# Arduino_extension_connectors.net
KiCad netlist of a schematic drawn in Altium Designer
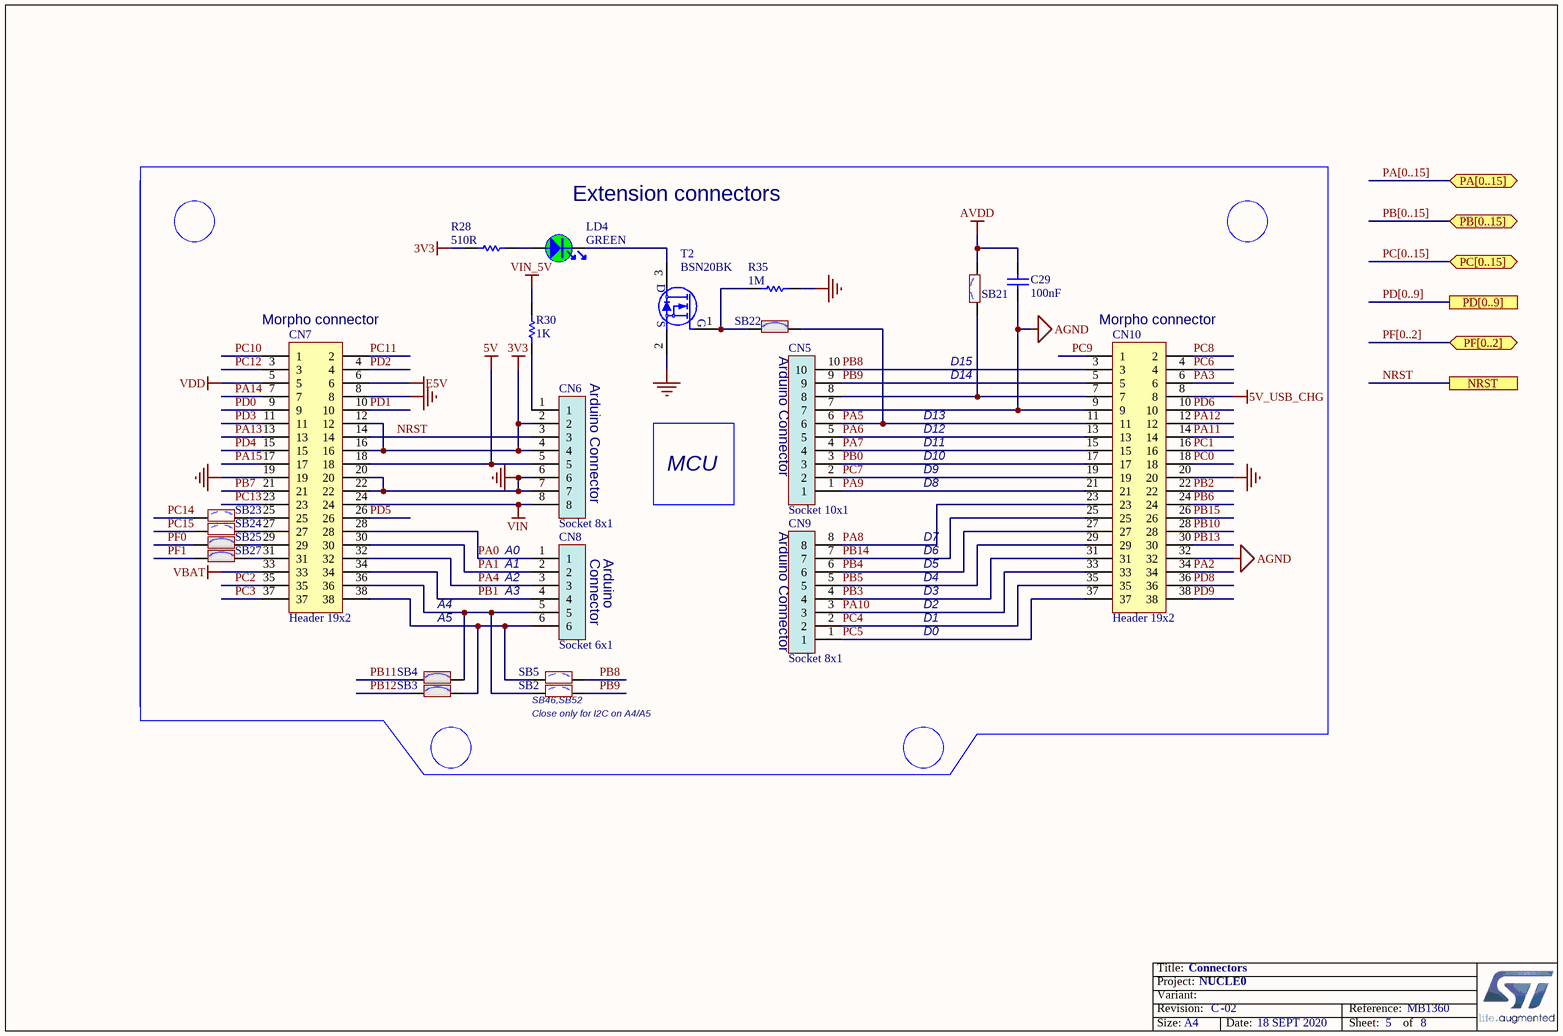
[diagram p0: Arduino_extension_connectors.SchDoc]

(export (version "E")
  (design (tool "Eeschema 10.0.6"))
  (components
    (comp (ref "C29")
      (value "100nF")
      (footprint "C0603")
      (description "Capacitor, MLCC, 100nF, 16V, X7R, 10%, 0603, T=0,8mm")
      (fields
        (field (name "INTERNAL_PART_NUMBER") "MCD-00211")
        (field (name "MANUFACTURER_PART_NUMBER") "CC0603KRX7R7BB104")
        (field (name "PROVIDED_BY") "SUBCO")
      )
      (libsource (lib "MCD_PARTS_database") (part "Capacitor"))
    )
    (comp (ref "CN5")
      (value "Socket 10x1")
      (footprint "CON_SAMTEC_SSW-110-03-X-S")
      (description "Socket, 10x1, 2.54mm, VR, TH, Height 8.51mm/10mm")
      (fields
        (field (name "INTERNAL_PART_NUMBER") "MCD-00262")
        (field (name "MANUFACTURER_PART_NUMBER") "SSW-110-03-x-S")
        (field (name "PROVIDED_BY") "SUBCO")
      )
      (libsource (lib "MCD_PARTS_database") (part "Socket 10x1"))
    )
    (comp (ref "CN6")
      (value "Socket 8x1")
      (footprint "CON_SAMTEC_SSW-108-03-X-S")
      (description "Socket, 8x1, 2.54mm, VR, TH, Height 8.51mm/10mm")
      (fields
        (field (name "INTERNAL_PART_NUMBER") "MCD-00261")
        (field (name "MANUFACTURER_PART_NUMBER") "SSW-108-03-x-S")
        (field (name "PROVIDED_BY") "SUBCO")
      )
      (libsource (lib "MCD_PARTS_database") (part "Socket 8x1"))
    )
    (comp (ref "CN7")
      (value "Header 19x2")
      (footprint "CON_SAMTEC_TSW-119-09-X-D")
      (description "Header, 19x2, 2,54mm, VR, TH, Height 5.84mm/10.16mm")
      (fields
        (field (name "INTERNAL_PART_NUMBER") "MCD-00213")
        (field (name "MANUFACTURER_PART_NUMBER") "TSW-119-09-x-D")
        (field (name "PROVIDED_BY") "SUBCO")
      )
      (libsource (lib "MCD_PARTS_database") (part "Header 19x2"))
    )
    (comp (ref "CN8")
      (value "Socket 6x1")
      (footprint "CON_SAMTEC_SSW-106-03-X-S")
      (description "Socket, 6x1, 2.54mm, VR, TH, Height 8.51mm/10mm")
      (fields
        (field (name "INTERNAL_PART_NUMBER") "MCD-00260")
        (field (name "MANUFACTURER_PART_NUMBER") "SSW-106-03-x-S")
        (field (name "PROVIDED_BY") "SUBCO")
      )
      (libsource (lib "MCD_PARTS_database") (part "Socket 6x1"))
    )
    (comp (ref "CN9")
      (value "Socket 8x1")
      (footprint "CON_SAMTEC_SSW-108-03-X-S")
      (description "Socket, 8x1, 2.54mm, VR, TH, Height 8.51mm/10mm")
      (fields
        (field (name "INTERNAL_PART_NUMBER") "MCD-00261")
        (field (name "MANUFACTURER_PART_NUMBER") "SSW-108-03-x-S")
        (field (name "PROVIDED_BY") "SUBCO")
      )
      (libsource (lib "") (part "Socket 8x1_1"))
    )
    (comp (ref "CN10")
      (value "Header 19x2")
      (footprint "CON_SAMTEC_TSW-119-09-X-D")
      (description "Header, 19x2, 2,54mm, VR, TH, Height 5.84mm/10.16mm")
      (fields
        (field (name "INTERNAL_PART_NUMBER") "MCD-00213")
        (field (name "MANUFACTURER_PART_NUMBER") "TSW-119-09-x-D")
        (field (name "PROVIDED_BY") "SUBCO")
      )
      (libsource (lib "MCD_PARTS_database") (part "Header 19x2"))
    )
    (comp (ref "LD4")
      (value "GREEN")
      (footprint "LED_0603_GREEN")
      (description "LED, Green, 0603")
      (fields
        (field (name "INTERNAL_PART_NUMBER") "MCD-00050")
        (field (name "MANUFACTURER_PART_NUMBER") "19-213SYGC/S530-E2/TR8")
        (field (name "PROVIDED_BY") "SUBCO")
      )
      (libsource (lib "MCD_PARTS_database") (part "LED_green"))
    )
    (comp (ref "R28")
      (value "510R")
      (footprint "R0603")
      (description "Resistor,510R,0603,1%,1/10W")
      (fields
        (field (name "INTERNAL_PART_NUMBER") "MCD-00225")
        (field (name "MANUFACTURER_PART_NUMBER") "RC0603FR-07510RL")
        (field (name "PROVIDED_BY") "SUBCO")
      )
      (libsource (lib "MCD_PARTS_database") (part "Resistor"))
    )
    (comp (ref "R30")
      (value "1K")
      (footprint "R0603")
      (description "Resistor,1K,0603,1%,1/10W")
      (fields
        (field (name "INTERNAL_PART_NUMBER") "MCD-00070")
        (field (name "MANUFACTURER_PART_NUMBER") "RC0603FR-071KL")
        (field (name "PROVIDED_BY") "SUBCO")
      )
      (libsource (lib "MCD_PARTS_database") (part "Resistor"))
    )
    (comp (ref "R35")
      (value "1M")
      (footprint "R0603")
      (description "Resistor,1M,0603,1%,1/10W")
      (fields
        (field (name "INTERNAL_PART_NUMBER") "MCD-00257")
        (field (name "MANUFACTURER_PART_NUMBER") "RC0603FR-071ML")
        (field (name "PROVIDED_BY") "SUBCO")
      )
      (libsource (lib "MCD_PARTS_database") (part "Resistor"))
    )
    (comp (ref "SB2")
      (value "SB_OFF")
      (footprint "SOLDER-BRIDGE_R0603-0R")
      (description "Solder Bridge OFF")
      (fields
        (field (name "INTERNAL_PART_NUMBER") "MCD-00072")
        (field (name "MANUFACTURER_PART_NUMBER") "RC0603JR-070RL")
        (field (name "PROVIDED_BY") "SUBCO")
      )
      (libsource (lib "MCD_PARTS_database") (part "SB_OFF"))
    )
    (comp (ref "SB3")
      (value "SB_ON")
      (footprint "SOLDER-BRIDGE_R0603-0R")
      (description "Solder Bridge ON")
      (fields
        (field (name "INTERNAL_PART_NUMBER") "MCD-00071")
        (field (name "MANUFACTURER_PART_NUMBER") "RC0603JR-070RL")
        (field (name "PROVIDED_BY") "SUBCO")
      )
      (libsource (lib "MCD_PARTS_database") (part "SB_ON"))
    )
    (comp (ref "SB4")
      (value "SB_ON")
      (footprint "SOLDER-BRIDGE_R0603-0R")
      (description "Solder Bridge ON")
      (fields
        (field (name "INTERNAL_PART_NUMBER") "MCD-00071")
        (field (name "MANUFACTURER_PART_NUMBER") "RC0603JR-070RL")
        (field (name "PROVIDED_BY") "SUBCO")
      )
      (libsource (lib "MCD_PARTS_database") (part "SB_ON"))
    )
    (comp (ref "SB5")
      (value "SB_OFF")
      (footprint "SOLDER-BRIDGE_R0603-0R")
      (description "Solder Bridge OFF")
      (fields
        (field (name "INTERNAL_PART_NUMBER") "MCD-00072")
        (field (name "MANUFACTURER_PART_NUMBER") "RC0603JR-070RL")
        (field (name "PROVIDED_BY") "SUBCO")
      )
      (libsource (lib "MCD_PARTS_database") (part "SB_OFF"))
    )
    (comp (ref "SB21")
      (value "SB_OFF")
      (footprint "SOLDER-BRIDGE_R0603-0R")
      (description "Solder Bridge OFF")
      (fields
        (field (name "INTERNAL_PART_NUMBER") "MCD-00072")
        (field (name "MANUFACTURER_PART_NUMBER") "RC0603JR-070RL")
        (field (name "PROVIDED_BY") "SUBCO")
      )
      (libsource (lib "") (part "SB_OFF_1"))
    )
    (comp (ref "SB22")
      (value "SB_ON")
      (footprint "SOLDER-BRIDGE_R0603-0R")
      (description "Solder Bridge ON")
      (fields
        (field (name "INTERNAL_PART_NUMBER") "MCD-00071")
        (field (name "MANUFACTURER_PART_NUMBER") "RC0603JR-070RL")
        (field (name "PROVIDED_BY") "SUBCO")
      )
      (libsource (lib "MCD_PARTS_database") (part "SB_ON"))
    )
    (comp (ref "SB23")
      (value "SB_OFF")
      (footprint "SOLDER-BRIDGE_R0603-0R")
      (description "Solder Bridge OFF")
      (fields
        (field (name "INTERNAL_PART_NUMBER") "MCD-00072")
        (field (name "MANUFACTURER_PART_NUMBER") "RC0603JR-070RL")
        (field (name "PROVIDED_BY") "SUBCO")
      )
      (libsource (lib "MCD_PARTS_database") (part "SB_OFF"))
    )
    (comp (ref "SB24")
      (value "SB_OFF")
      (footprint "SOLDER-BRIDGE_R0603-0R")
      (description "Solder Bridge OFF")
      (fields
        (field (name "INTERNAL_PART_NUMBER") "MCD-00072")
        (field (name "MANUFACTURER_PART_NUMBER") "RC0603JR-070RL")
        (field (name "PROVIDED_BY") "SUBCO")
      )
      (libsource (lib "MCD_PARTS_database") (part "SB_OFF"))
    )
    (comp (ref "SB25")
      (value "SB_ON")
      (footprint "SOLDER-BRIDGE_R0603-0R")
      (description "Solder Bridge ON")
      (fields
        (field (name "INTERNAL_PART_NUMBER") "MCD-00071")
        (field (name "MANUFACTURER_PART_NUMBER") "RC0603JR-070RL")
        (field (name "PROVIDED_BY") "SUBCO")
      )
      (libsource (lib "MCD_PARTS_database") (part "SB_ON"))
    )
    (comp (ref "SB27")
      (value "SB_ON")
      (footprint "SOLDER-BRIDGE_R0603-0R")
      (description "Solder Bridge ON")
      (fields
        (field (name "INTERNAL_PART_NUMBER") "MCD-00071")
        (field (name "MANUFACTURER_PART_NUMBER") "RC0603JR-070RL")
        (field (name "PROVIDED_BY") "SUBCO")
      )
      (libsource (lib "MCD_PARTS_database") (part "SB_ON"))
    )
    (comp (ref "T2")
      (value "BSN20BK")
      (footprint "MOS_SOT23")
      (description "N-channel enhancement mode field-effect transistor")
      (fields
        (field (name "INTERNAL_PART_NUMBER") "MCD-01969")
        (field (name "MANUFACTURER") "NEXPERIA")
        (field (name "PROVIDED_BY") "SUBCO")
      )
      (libsource (lib "MCD_PARTS_database") (part "BSN20"))
    )
  )
  (nets
    (net (code "3") (name "/NRST") (class "Default")
      (node (ref "CN6") (pin "3") (pinfunction "3_3") (pintype "passive"))
      (node (ref "CN7") (pin "14") (pinfunction "14_14") (pintype "passive"))
    )
    (net (code "4") (name "/PA0") (class "Default")
      (node (ref "CN7") (pin "28") (pinfunction "28_28") (pintype "passive"))
      (node (ref "CN8") (pin "1") (pinfunction "1_1") (pintype "passive"))
    )
    (net (code "5") (name "/PA1") (class "Default")
      (node (ref "CN7") (pin "30") (pinfunction "30_30") (pintype "passive"))
      (node (ref "CN8") (pin "2") (pinfunction "2_2") (pintype "passive"))
    )
    (net (code "6") (name "/PA2") (class "Default")
      (node (ref "CN10") (pin "34") (pinfunction "34_34") (pintype "passive"))
    )
    (net (code "7") (name "/PA3") (class "Default")
      (node (ref "CN10") (pin "6") (pinfunction "6_6") (pintype "passive"))
    )
    (net (code "8") (name "/PA4") (class "Default")
      (node (ref "CN7") (pin "32") (pinfunction "32_32") (pintype "passive"))
      (node (ref "CN8") (pin "3") (pinfunction "3_3") (pintype "passive"))
    )
    (net (code "9") (name "/PA5") (class "Default")
      (node (ref "CN10") (pin "11") (pinfunction "11_11") (pintype "passive"))
      (node (ref "CN5") (pin "6") (pinfunction "6_6") (pintype "passive"))
      (node (ref "SB22") (pin "2") (pinfunction "2_2") (pintype "passive"))
    )
    (net (code "10") (name "/PA6") (class "Default")
      (node (ref "CN10") (pin "13") (pinfunction "13_13") (pintype "passive"))
      (node (ref "CN5") (pin "5") (pinfunction "5_5") (pintype "passive"))
    )
    (net (code "11") (name "/PA7") (class "Default")
      (node (ref "CN10") (pin "15") (pinfunction "15_15") (pintype "passive"))
      (node (ref "CN5") (pin "4") (pinfunction "4_4") (pintype "passive"))
    )
    (net (code "12") (name "/PA8") (class "Default")
      (node (ref "CN10") (pin "23") (pinfunction "23_23") (pintype "passive"))
      (node (ref "CN9") (pin "8") (pinfunction "8_8") (pintype "passive"))
    )
    (net (code "13") (name "/PA9") (class "Default")
      (node (ref "CN10") (pin "21") (pinfunction "21_21") (pintype "passive"))
      (node (ref "CN5") (pin "1") (pinfunction "1_1") (pintype "passive"))
    )
    (net (code "14") (name "/PA10") (class "Default")
      (node (ref "CN10") (pin "33") (pinfunction "33_33") (pintype "passive"))
      (node (ref "CN9") (pin "3") (pinfunction "3_3") (pintype "passive"))
    )
    (net (code "15") (name "/PA11") (class "Default")
      (node (ref "CN10") (pin "14") (pinfunction "14_14") (pintype "passive"))
    )
    (net (code "16") (name "/PA12") (class "Default")
      (node (ref "CN10") (pin "12") (pinfunction "12_12") (pintype "passive"))
    )
    (net (code "17") (name "/PA13") (class "Default")
      (node (ref "CN7") (pin "13") (pinfunction "13_13") (pintype "passive"))
    )
    (net (code "18") (name "/PA14") (class "Default")
      (node (ref "CN7") (pin "7") (pinfunction "7_7") (pintype "passive"))
    )
    (net (code "19") (name "/PA15") (class "Default")
      (node (ref "CN7") (pin "17") (pinfunction "17_17") (pintype "passive"))
    )
    (net (code "21") (name "/PB0") (class "Default")
      (node (ref "CN10") (pin "17") (pinfunction "17_17") (pintype "passive"))
      (node (ref "CN5") (pin "3") (pinfunction "3_3") (pintype "passive"))
    )
    (net (code "22") (name "/PB1") (class "Default")
      (node (ref "CN7") (pin "34") (pinfunction "34_34") (pintype "passive"))
      (node (ref "CN8") (pin "4") (pinfunction "4_4") (pintype "passive"))
    )
    (net (code "23") (name "/PB2") (class "Default")
      (node (ref "CN10") (pin "22") (pinfunction "22_22") (pintype "passive"))
    )
    (net (code "24") (name "/PB3") (class "Default")
      (node (ref "CN10") (pin "31") (pinfunction "31_31") (pintype "passive"))
      (node (ref "CN9") (pin "4") (pinfunction "4_4") (pintype "passive"))
    )
    (net (code "25") (name "/PB4") (class "Default")
      (node (ref "CN10") (pin "27") (pinfunction "27_27") (pintype "passive"))
      (node (ref "CN9") (pin "6") (pinfunction "6_6") (pintype "passive"))
    )
    (net (code "26") (name "/PB5") (class "Default")
      (node (ref "CN10") (pin "29") (pinfunction "29_29") (pintype "passive"))
      (node (ref "CN9") (pin "5") (pinfunction "5_5") (pintype "passive"))
    )
    (net (code "27") (name "/PB6") (class "Default")
      (node (ref "CN10") (pin "24") (pinfunction "24_24") (pintype "passive"))
    )
    (net (code "28") (name "/PB7") (class "Default")
      (node (ref "CN7") (pin "21") (pinfunction "21_21") (pintype "passive"))
    )
    (net (code "29") (name "/PB8") (class "Default")
      (node (ref "CN10") (pin "3") (pinfunction "3_3") (pintype "passive"))
      (node (ref "CN5") (pin "10") (pinfunction "10_10") (pintype "passive"))
      (node (ref "SB5") (pin "2") (pinfunction "2_2") (pintype "passive"))
    )
    (net (code "30") (name "/PB9") (class "Default")
      (node (ref "CN10") (pin "5") (pinfunction "5_5") (pintype "passive"))
      (node (ref "CN5") (pin "9") (pinfunction "9_9") (pintype "passive"))
      (node (ref "SB2") (pin "2") (pinfunction "2_2") (pintype "passive"))
    )
    (net (code "31") (name "/PB10") (class "Default")
      (node (ref "CN10") (pin "28") (pinfunction "28_28") (pintype "passive"))
    )
    (net (code "32") (name "/PB11") (class "Default")
      (node (ref "SB4") (pin "1") (pinfunction "1_1") (pintype "passive"))
    )
    (net (code "33") (name "/PB12") (class "Default")
      (node (ref "SB3") (pin "1") (pinfunction "1_1") (pintype "passive"))
    )
    (net (code "34") (name "/PB13") (class "Default")
      (node (ref "CN10") (pin "30") (pinfunction "30_30") (pintype "passive"))
    )
    (net (code "35") (name "/PB14") (class "Default")
      (node (ref "CN10") (pin "25") (pinfunction "25_25") (pintype "passive"))
      (node (ref "CN9") (pin "7") (pinfunction "7_7") (pintype "passive"))
    )
    (net (code "36") (name "/PB15") (class "Default")
      (node (ref "CN10") (pin "26") (pinfunction "26_26") (pintype "passive"))
    )
    (net (code "38") (name "/PC0") (class "Default")
      (node (ref "CN10") (pin "18") (pinfunction "18_18") (pintype "passive"))
    )
    (net (code "39") (name "/PC1") (class "Default")
      (node (ref "CN10") (pin "16") (pinfunction "16_16") (pintype "passive"))
    )
    (net (code "40") (name "/PC2") (class "Default")
      (node (ref "CN7") (pin "35") (pinfunction "35_35") (pintype "passive"))
    )
    (net (code "41") (name "/PC3") (class "Default")
      (node (ref "CN7") (pin "37") (pinfunction "37_37") (pintype "passive"))
    )
    (net (code "42") (name "/PC4") (class "Default")
      (node (ref "CN10") (pin "35") (pinfunction "35_35") (pintype "passive"))
      (node (ref "CN9") (pin "2") (pinfunction "2_2") (pintype "passive"))
    )
    (net (code "43") (name "/PC5") (class "Default")
      (node (ref "CN10") (pin "37") (pinfunction "37_37") (pintype "passive"))
      (node (ref "CN9") (pin "1") (pinfunction "1_1") (pintype "passive"))
    )
    (net (code "44") (name "/PC6") (class "Default")
      (node (ref "CN10") (pin "4") (pinfunction "4_4") (pintype "passive"))
    )
    (net (code "45") (name "/PC7") (class "Default")
      (node (ref "CN10") (pin "19") (pinfunction "19_19") (pintype "passive"))
      (node (ref "CN5") (pin "2") (pinfunction "2_2") (pintype "passive"))
    )
    (net (code "46") (name "/PC8") (class "Default")
      (node (ref "CN10") (pin "2") (pinfunction "2_2") (pintype "passive"))
    )
    (net (code "47") (name "/PC9") (class "Default")
      (node (ref "CN10") (pin "1") (pinfunction "1_1") (pintype "passive"))
    )
    (net (code "48") (name "/PC10") (class "Default")
      (node (ref "CN7") (pin "1") (pinfunction "1_1") (pintype "passive"))
    )
    (net (code "49") (name "/PC11") (class "Default")
      (node (ref "CN7") (pin "2") (pinfunction "2_2") (pintype "passive"))
    )
    (net (code "50") (name "/PC12") (class "Default")
      (node (ref "CN7") (pin "3") (pinfunction "3_3") (pintype "passive"))
    )
    (net (code "51") (name "/PC13") (class "Default")
      (node (ref "CN7") (pin "23") (pinfunction "23_23") (pintype "passive"))
    )
    (net (code "52") (name "/PC14") (class "Default")
      (node (ref "SB23") (pin "1") (pinfunction "1_1") (pintype "passive"))
    )
    (net (code "53") (name "/PC15") (class "Default")
      (node (ref "SB24") (pin "1") (pinfunction "1_1") (pintype "passive"))
    )
    (net (code "55") (name "/PD0") (class "Default")
      (node (ref "CN7") (pin "9") (pinfunction "9_9") (pintype "passive"))
    )
    (net (code "56") (name "/PD1") (class "Default")
      (node (ref "CN7") (pin "10") (pinfunction "10_10") (pintype "passive"))
    )
    (net (code "57") (name "/PD2") (class "Default")
      (node (ref "CN7") (pin "4") (pinfunction "4_4") (pintype "passive"))
    )
    (net (code "58") (name "/PD3") (class "Default")
      (node (ref "CN7") (pin "11") (pinfunction "11_11") (pintype "passive"))
    )
    (net (code "59") (name "/PD4") (class "Default")
      (node (ref "CN7") (pin "15") (pinfunction "15_15") (pintype "passive"))
    )
    (net (code "60") (name "/PD5") (class "Default")
      (node (ref "CN7") (pin "26") (pinfunction "26_26") (pintype "passive"))
    )
    (net (code "61") (name "/PD6") (class "Default")
      (node (ref "CN10") (pin "10") (pinfunction "10_10") (pintype "passive"))
    )
    (net (code "62") (name "/PD8") (class "Default")
      (node (ref "CN10") (pin "36") (pinfunction "36_36") (pintype "passive"))
    )
    (net (code "63") (name "/PD9") (class "Default")
      (node (ref "CN10") (pin "38") (pinfunction "38_38") (pintype "passive"))
    )
    (net (code "65") (name "/PF0") (class "Default")
      (node (ref "SB25") (pin "1") (pinfunction "1_1") (pintype "passive"))
    )
    (net (code "66") (name "/PF1") (class "Default")
      (node (ref "SB27") (pin "1") (pinfunction "1_1") (pintype "passive"))
    )
    (net (code "68") (name "3V3") (class "Default")
      (node (ref "CN6") (pin "2") (pinfunction "2_2") (pintype "passive"))
      (node (ref "CN6") (pin "4") (pinfunction "4_4") (pintype "passive"))
      (node (ref "CN7") (pin "12") (pinfunction "12_12") (pintype "passive"))
      (node (ref "CN7") (pin "16") (pinfunction "16_16") (pintype "passive"))
      (node (ref "R28") (pin "2") (pinfunction "2_2") (pintype "passive"))
    )
    (net (code "69") (name "5V") (class "Default")
      (node (ref "CN6") (pin "5") (pinfunction "5_5") (pintype "passive"))
      (node (ref "CN7") (pin "18") (pinfunction "18_18") (pintype "passive"))
    )
    (net (code "70") (name "5V_USB_CHG") (class "Default")
      (node (ref "CN10") (pin "8") (pinfunction "8_8") (pintype "passive"))
    )
    (net (code "71") (name "AGND") (class "Default")
      (node (ref "C29") (pin "1") (pinfunction "1_1") (pintype "passive"))
      (node (ref "CN10") (pin "32") (pinfunction "32_32") (pintype "passive"))
      (node (ref "CN10") (pin "9") (pinfunction "9_9") (pintype "passive"))
      (node (ref "CN5") (pin "7") (pinfunction "7_7") (pintype "passive"))
    )
    (net (code "72") (name "AVDD") (class "Default")
      (node (ref "C29") (pin "2") (pinfunction "2_2") (pintype "passive"))
      (node (ref "SB21") (pin "2") (pinfunction "2_2") (pintype "passive"))
    )
    (net (code "73") (name "E5V") (class "Default")
      (node (ref "CN7") (pin "6") (pinfunction "6_6") (pintype "passive"))
    )
    (net (code "74") (name "GND") (class "Default")
      (node (ref "CN10") (pin "20") (pinfunction "20_20") (pintype "passive"))
      (node (ref "CN6") (pin "6") (pinfunction "6_6") (pintype "passive"))
      (node (ref "CN6") (pin "7") (pinfunction "7_7") (pintype "passive"))
      (node (ref "CN7") (pin "19") (pinfunction "19_19") (pintype "passive"))
      (node (ref "CN7") (pin "20") (pinfunction "20_20") (pintype "passive"))
      (node (ref "CN7") (pin "22") (pinfunction "22_22") (pintype "passive"))
      (node (ref "CN7") (pin "8") (pinfunction "8_8") (pintype "passive"))
      (node (ref "R35") (pin "2") (pinfunction "2_2") (pintype "passive"))
      (node (ref "T2") (pin "2") (pinfunction "S_2") (pintype "passive"))
    )
    (net (code "75") (name "Net-(CN6-Pad1)") (class "Default")
      (node (ref "CN6") (pin "1") (pinfunction "1_1") (pintype "passive"))
      (node (ref "R30") (pin "2") (pinfunction "2_2") (pintype "passive"))
    )
    (net (code "76") (name "Net-(CN7-Pad25)") (class "Default")
      (node (ref "CN7") (pin "25") (pinfunction "25_25") (pintype "passive"))
      (node (ref "SB23") (pin "2") (pinfunction "2_2") (pintype "passive"))
    )
    (net (code "77") (name "Net-(CN7-Pad27)") (class "Default")
      (node (ref "CN7") (pin "27") (pinfunction "27_27") (pintype "passive"))
      (node (ref "SB24") (pin "2") (pinfunction "2_2") (pintype "passive"))
    )
    (net (code "78") (name "Net-(CN7-Pad29)") (class "Default")
      (node (ref "CN7") (pin "29") (pinfunction "29_29") (pintype "passive"))
      (node (ref "SB25") (pin "2") (pinfunction "2_2") (pintype "passive"))
    )
    (net (code "79") (name "Net-(CN7-Pad31)") (class "Default")
      (node (ref "CN7") (pin "31") (pinfunction "31_31") (pintype "passive"))
      (node (ref "SB27") (pin "2") (pinfunction "2_2") (pintype "passive"))
    )
    (net (code "80") (name "Net-(CN7-Pad36)") (class "Default")
      (node (ref "CN7") (pin "36") (pinfunction "36_36") (pintype "passive"))
      (node (ref "CN8") (pin "5") (pinfunction "5_5") (pintype "passive"))
      (node (ref "SB2") (pin "1") (pinfunction "1_1") (pintype "passive"))
      (node (ref "SB4") (pin "2") (pinfunction "2_2") (pintype "passive"))
    )
    (net (code "81") (name "Net-(CN7-Pad38)") (class "Default")
      (node (ref "CN7") (pin "38") (pinfunction "38_38") (pintype "passive"))
      (node (ref "CN8") (pin "6") (pinfunction "6_6") (pintype "passive"))
      (node (ref "SB3") (pin "2") (pinfunction "2_2") (pintype "passive"))
      (node (ref "SB5") (pin "1") (pinfunction "1_1") (pintype "passive"))
    )
    (net (code "82") (name "Net-(CN10-Pad7)") (class "Default")
      (node (ref "CN10") (pin "7") (pinfunction "7_7") (pintype "passive"))
      (node (ref "CN5") (pin "8") (pinfunction "8_8") (pintype "passive"))
      (node (ref "SB21") (pin "1") (pinfunction "1_1") (pintype "passive"))
    )
    (net (code "83") (name "Net-(LD4-Pad1)") (class "Default")
      (node (ref "LD4") (pin "1") (pintype "passive"))
      (node (ref "R28") (pin "1") (pinfunction "1_1") (pintype "passive"))
    )
    (net (code "84") (name "Net-(T2-D)") (class "Default")
      (node (ref "LD4") (pin "2") (pintype "passive"))
      (node (ref "T2") (pin "3") (pinfunction "D_3") (pintype "passive"))
    )
    (net (code "85") (name "Net-(T2-G)") (class "Default")
      (node (ref "R35") (pin "1") (pinfunction "1_1") (pintype "passive"))
      (node (ref "SB22") (pin "1") (pinfunction "1_1") (pintype "passive"))
      (node (ref "T2") (pin "1") (pinfunction "G_1") (pintype "passive"))
    )
    (net (code "86") (name "VBAT") (class "Default")
      (node (ref "CN7") (pin "33") (pinfunction "33_33") (pintype "passive"))
    )
    (net (code "87") (name "VDD") (class "Default")
      (node (ref "CN7") (pin "5") (pinfunction "5_5") (pintype "passive"))
    )
    (net (code "88") (name "VIN") (class "Default")
      (node (ref "CN6") (pin "8") (pinfunction "8_8") (pintype "passive"))
      (node (ref "CN7") (pin "24") (pinfunction "24_24") (pintype "passive"))
    )
    (net (code "89") (name "VIN_5V") (class "Default")
      (node (ref "R30") (pin "1") (pinfunction "1_1") (pintype "passive"))
    )
  )
)
